# voltage_regulator.net
KiCad netlist of a schematic drawn in Altium Designer
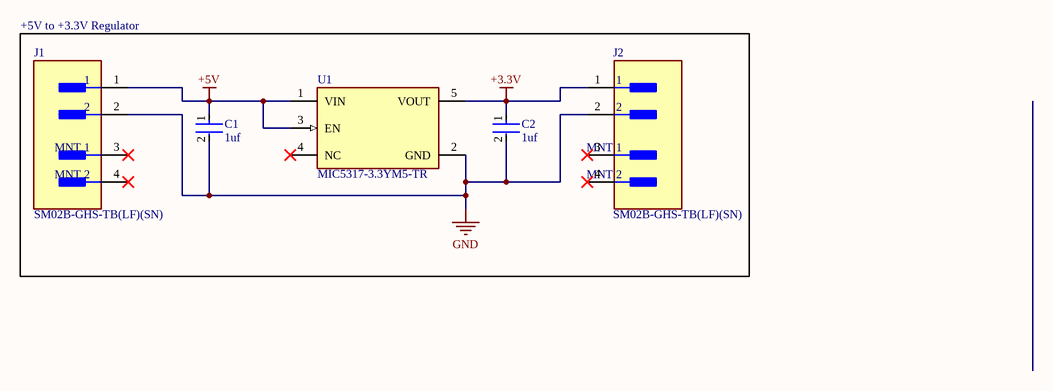
[diagram p0: voltage regulator.SchDoc]

(export (version "E")
  (design (tool "Eeschema 10.0.6"))
  (components
    (comp (ref "C1")
      (value "1uf")
      (footprint "FP-CC0805-0_85-MFG")
      (description "CC0805 1 uF X5R 10.00% 6.3 V")
      (fields (field (name "MANUFACTURER") "Yageo"))
      (libsource (lib "Altium Content Vault") (part "11868f565c42a9108669ba33697ecf6"))
    )
    (comp (ref "C2")
      (value "1uf")
      (footprint "FP-CC0805-0_85-MFG")
      (description "CC0805 1 uF X5R 10.00% 6.3 V")
      (fields (field (name "MANUFACTURER") "Yageo"))
      (libsource (lib "Altium Content Vault") (part "11868f565c42a9108669ba33697ecf6"))
    )
    (comp (ref "J1")
      (value "SM02B-GHS-TB(LF)(SN)")
      (footprint "FP-SM02B-GHS-TB_LF_SN-MFG")
      (description "CONN HEADER SMD R/A 2POS 1.25MM")
      (libsource (lib "") (part "56ec3178a87b3978bdc1b3682cd516a_1"))
    )
    (comp (ref "J2")
      (value "SM02B-GHS-TB(LF)(SN)")
      (footprint "FP-SM02B-GHS-TB_LF_SN-MFG")
      (description "CONN HEADER SMD R/A 2POS 1.25MM")
      (libsource (lib "Altium Content Vault") (part "56ec3178a87b3978bdc1b3682cd516a"))
    )
    (comp (ref "U1")
      (value "MIC5317-3.3YM5-TR")
      (footprint "FP-SOT23-5LD-PL-1-MFG")
      (description "IC REG LINEAR 3.3V 150MA SOT23-5")
      (libsource (lib "Altium Content Vault") (part "0a093dae7315cdc977fd108dde87457"))
    )
  )
  (nets
    (net (code "1") (name "+3.3V") (class "Default")
      (node (ref "C2") (pin "1") (pinfunction "1_1") (pintype "passive"))
      (node (ref "J2") (pin "1") (pinfunction "1_1") (pintype "passive"))
      (node (ref "U1") (pin "5") (pinfunction "VOUT_5") (pintype "power_in"))
    )
    (net (code "2") (name "+5V") (class "Default")
      (node (ref "C1") (pin "1") (pinfunction "1_1") (pintype "passive"))
      (node (ref "J1") (pin "1") (pinfunction "1_1") (pintype "passive"))
      (node (ref "U1") (pin "1") (pinfunction "VIN_1") (pintype "power_in"))
      (node (ref "U1") (pin "3") (pinfunction "EN_3") (pintype "input"))
    )
    (net (code "3") (name "GND") (class "Default")
      (node (ref "C1") (pin "2") (pinfunction "2_2") (pintype "passive"))
      (node (ref "C2") (pin "2") (pinfunction "2_2") (pintype "passive"))
      (node (ref "J1") (pin "2") (pinfunction "2_2") (pintype "passive"))
      (node (ref "J2") (pin "2") (pinfunction "2_2") (pintype "passive"))
      (node (ref "U1") (pin "2") (pinfunction "GND_2") (pintype "power_in"))
    )
    (net (code "4") (name "unconnected-(J1-MNT_1-Pad3)") (class "Default")
      (node (ref "J1") (pin "3") (pinfunction "MNT_1_3") (pintype "passive+no_connect"))
    )
    (net (code "5") (name "unconnected-(J1-MNT_2-Pad4)") (class "Default")
      (node (ref "J1") (pin "4") (pinfunction "MNT_2_4") (pintype "passive+no_connect"))
    )
    (net (code "6") (name "unconnected-(J2-MNT_1-Pad3)") (class "Default")
      (node (ref "J2") (pin "3") (pinfunction "MNT_1_3") (pintype "passive+no_connect"))
    )
    (net (code "7") (name "unconnected-(J2-MNT_2-Pad4)") (class "Default")
      (node (ref "J2") (pin "4") (pinfunction "MNT_2_4") (pintype "passive+no_connect"))
    )
    (net (code "8") (name "unconnected-(U1-NC-Pad4)") (class "Default")
      (node (ref "U1") (pin "4") (pinfunction "NC_4") (pintype "passive+no_connect"))
    )
  )
)
